# LTC1514_3V3_pompa.net
KiCad netlist of a schematic drawn in EAGLE
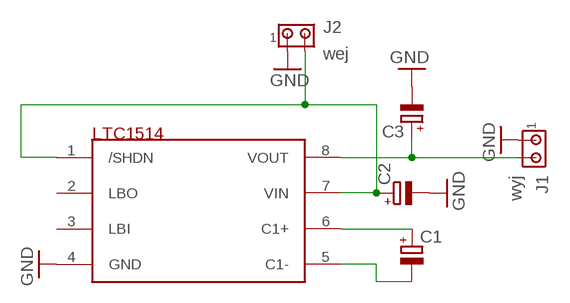
[diagram p0: schematic, sheet 1]

(export (version "E")
  (design (tool "Eeschema 10.0.6"))
  (components
    (comp (ref "C1")
      (value "CPOL-EUE2,5-6E")
      (footprint "eagle-import:E2,5-6E")
      (libsource (lib "eagle-import") (part "CPOL-EUE2,5-6E"))
    )
    (comp (ref "C2")
      (value "CPOL-EUE2,5-6E")
      (footprint "eagle-import:E2,5-6E")
      (libsource (lib "eagle-import") (part "CPOL-EUE2,5-6E"))
    )
    (comp (ref "C3")
      (value "CPOL-EUE2,5-6E")
      (footprint "eagle-import:E2,5-6E")
      (libsource (lib "eagle-import") (part "CPOL-EUE2,5-6E"))
    )
    (comp (ref "J1")
      (value "wyj")
      (footprint "eagle-import:10X02MTA")
      (libsource (lib "eagle-import") (part "MTA02-100"))
    )
    (comp (ref "J2")
      (value "wej")
      (footprint "eagle-import:10X02MTA")
      (libsource (lib "eagle-import") (part "MTA02-100"))
    )
    (comp (ref "U$1")
      (value "LTC1514")
      (footprint "eagle-import:SO08")
      (libsource (lib "eagle-import") (part "LTC1514"))
    )
  )
  (nets
    (net (code "1") (name "GND") (class "Default")
      (node (ref "C2") (pin "-") (pinfunction "-_-") (pintype "passive"))
      (node (ref "C3") (pin "-") (pinfunction "-_-") (pintype "passive"))
      (node (ref "J1") (pin "1") (pinfunction "1_1") (pintype "passive"))
      (node (ref "J2") (pin "1") (pinfunction "1_1") (pintype "passive"))
      (node (ref "U$1") (pin "4") (pinfunction "GND_4") (pintype "bidirectional"))
    )
    (net (code "2") (name "Net-(U$1-C1+)") (class "Default")
      (node (ref "C1") (pin "+") (pinfunction "+_+") (pintype "passive"))
      (node (ref "U$1") (pin "6") (pinfunction "C1+_6") (pintype "bidirectional"))
    )
    (net (code "3") (name "Net-(U$1-C1-)") (class "Default")
      (node (ref "C1") (pin "-") (pinfunction "-_-") (pintype "passive"))
      (node (ref "U$1") (pin "5") (pinfunction "C1-_5") (pintype "bidirectional"))
    )
    (net (code "4") (name "Net-(U$1-VIN)") (class "Default")
      (node (ref "C2") (pin "+") (pinfunction "+_+") (pintype "passive"))
      (node (ref "J2") (pin "2") (pinfunction "2_2") (pintype "passive"))
      (node (ref "U$1") (pin "1") (pinfunction "/SHDN_1") (pintype "bidirectional"))
      (node (ref "U$1") (pin "7") (pinfunction "VIN_7") (pintype "bidirectional"))
    )
    (net (code "5") (name "Net-(U$1-VOUT)") (class "Default")
      (node (ref "C3") (pin "+") (pinfunction "+_+") (pintype "passive"))
      (node (ref "J1") (pin "2") (pinfunction "2_2") (pintype "passive"))
      (node (ref "U$1") (pin "8") (pinfunction "VOUT_8") (pintype "bidirectional"))
    )
    (net (code "6") (name "unconnected-(U$1-LBI-Pad3)") (class "Default")
      (node (ref "U$1") (pin "3") (pinfunction "LBI_3") (pintype "bidirectional"))
    )
    (net (code "7") (name "unconnected-(U$1-LBO-Pad2)") (class "Default")
      (node (ref "U$1") (pin "2") (pinfunction "LBO_2") (pintype "bidirectional"))
    )
  )
)
